# Uart_Can.net
KiCad netlist of a schematic drawn in Altium Designer
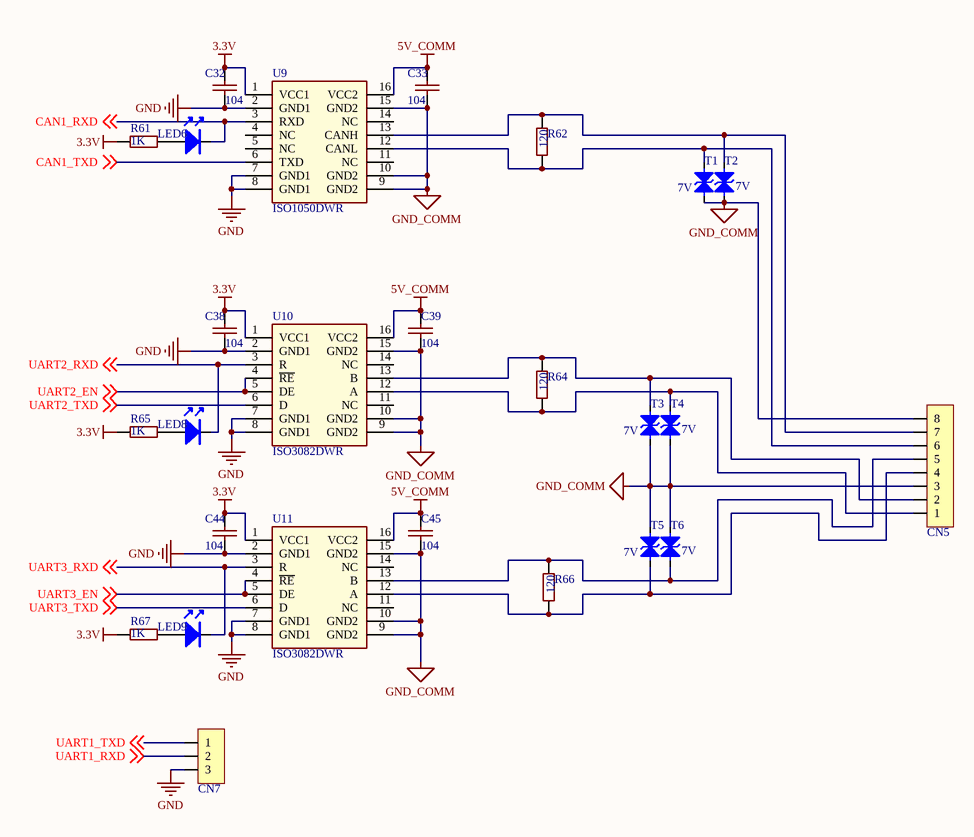
[diagram p0: Uart_Can.SchDoc]

(export (version "E")
  (design (tool "Eeschema 10.0.6"))
  (components
    (comp (ref "C32")
      (value "104")
      (footprint "0805SMD_Cap")
      (description "贴片电容")
      (libsource (lib "ST_GND_Sch") (part "SMD_Cap"))
    )
    (comp (ref "C33")
      (value "104")
      (footprint "0805SMD_Cap")
      (description "贴片电容")
      (libsource (lib "ST_GND_Sch") (part "SMD_Cap"))
    )
    (comp (ref "C38")
      (value "104")
      (footprint "0805SMD_Cap")
      (description "贴片电容")
      (libsource (lib "ST_GND_Sch") (part "SMD_Cap"))
    )
    (comp (ref "C39")
      (value "104")
      (footprint "0805SMD_Cap")
      (description "贴片电容")
      (libsource (lib "ST_GND_Sch") (part "SMD_Cap"))
    )
    (comp (ref "C44")
      (value "104")
      (footprint "0805SMD_Cap")
      (description "贴片电容")
      (libsource (lib "ST_GND_Sch") (part "SMD_Cap"))
    )
    (comp (ref "C45")
      (value "104")
      (footprint "0805SMD_Cap")
      (description "贴片电容")
      (libsource (lib "ST_GND_Sch") (part "SMD_Cap"))
    )
    (comp (ref "CN5")
      (value "CON8")
      (footprint "WJ15EDGRM-3.81-8P")
      (description "连接器")
      (libsource (lib "ST_GND_Sch") (part "CON8"))
    )
    (comp (ref "CN7")
      (value "CON3")
      (footprint "DIP3")
      (description "连接器")
      (libsource (lib "ST_GND_Sch") (part "CON3"))
    )
    (comp (ref "LED6")
      (value "LED")
      (footprint "发光二极管0805")
      (description "发光二极管")
      (libsource (lib "ST_GND_Sch") (part "LED"))
    )
    (comp (ref "LED8")
      (value "LED")
      (footprint "发光二极管0805")
      (description "发光二极管")
      (libsource (lib "ST_GND_Sch") (part "LED"))
    )
    (comp (ref "LED9")
      (value "LED")
      (footprint "发光二极管0805")
      (description "发光二极管")
      (libsource (lib "ST_GND_Sch") (part "LED"))
    )
    (comp (ref "R61")
      (value "1K")
      (footprint "0805_SMD_R")
      (description "贴片电阻")
      (libsource (lib "") (part "SMD_0805_1"))
    )
    (comp (ref "R62")
      (value "120")
      (footprint "0805_SMD_R")
      (description "贴片电阻")
      (libsource (lib "ST_GND_Sch") (part "SMD_0805"))
    )
    (comp (ref "R64")
      (value "120")
      (footprint "0805_SMD_R")
      (description "贴片电阻")
      (libsource (lib "ST_GND_Sch") (part "SMD_0805"))
    )
    (comp (ref "R65")
      (value "1K")
      (footprint "0805_SMD_R")
      (description "贴片电阻")
      (libsource (lib "") (part "SMD_0805_1"))
    )
    (comp (ref "R66")
      (value "120")
      (footprint "0805_SMD_R")
      (description "贴片电阻")
      (libsource (lib "ST_GND_Sch") (part "SMD_0805"))
    )
    (comp (ref "R67")
      (value "1K")
      (footprint "0805_SMD_R")
      (description "贴片电阻")
      (libsource (lib "") (part "SMD_0805_1"))
    )
    (comp (ref "T1")
      (value "7V")
      (footprint "二极管SMA")
      (description "双向TVS_?V(SMA)")
      (libsource (lib "ST_GND_Sch") (part "双向TVS_?V(SMA)"))
    )
    (comp (ref "T2")
      (value "7V")
      (footprint "二极管SMA")
      (description "双向TVS_?V(SMA)")
      (libsource (lib "ST_GND_Sch") (part "双向TVS_?V(SMA)"))
    )
    (comp (ref "T3")
      (value "7V")
      (footprint "二极管SMA")
      (description "双向TVS_?V(SMA)")
      (libsource (lib "ST_GND_Sch") (part "双向TVS_?V(SMA)"))
    )
    (comp (ref "T4")
      (value "7V")
      (footprint "二极管SMA")
      (description "双向TVS_?V(SMA)")
      (libsource (lib "ST_GND_Sch") (part "双向TVS_?V(SMA)"))
    )
    (comp (ref "T5")
      (value "7V")
      (footprint "二极管SMA")
      (description "双向TVS_?V(SMA)")
      (libsource (lib "ST_GND_Sch") (part "双向TVS_?V(SMA)"))
    )
    (comp (ref "T6")
      (value "7V")
      (footprint "二极管SMA")
      (description "双向TVS_?V(SMA)")
      (libsource (lib "ST_GND_Sch") (part "双向TVS_?V(SMA)"))
    )
    (comp (ref "U9")
      (value "ISO1050DWR")
      (footprint "SOIC_16")
      (description "CAN隔离芯片")
      (libsource (lib "ST_GND_Sch") (part "ISO1050DWR"))
    )
    (comp (ref "U10")
      (value "ISO3082DWR")
      (footprint "SOIC_16")
      (description "485隔离芯片")
      (libsource (lib "ST_GND_Sch") (part "ISO3082DWR"))
    )
    (comp (ref "U11")
      (value "ISO3082DWR")
      (footprint "SOIC_16")
      (description "485隔离芯片")
      (libsource (lib "ST_GND_Sch") (part "ISO3082DWR"))
    )
  )
  (nets
    (net (code "1") (name "3.3V") (class "Default")
      (node (ref "C32") (pin "2") (pintype "passive"))
      (node (ref "C38") (pin "2") (pintype "passive"))
      (node (ref "C44") (pin "2") (pintype "passive"))
      (node (ref "R61") (pin "2") (pinfunction "2_2") (pintype "passive"))
      (node (ref "R65") (pin "2") (pinfunction "2_2") (pintype "passive"))
      (node (ref "R67") (pin "2") (pinfunction "2_2") (pintype "passive"))
      (node (ref "U10") (pin "1") (pinfunction "VCC1_1") (pintype "passive"))
      (node (ref "U11") (pin "1") (pinfunction "VCC1_1") (pintype "passive"))
      (node (ref "U9") (pin "1") (pinfunction "VCC1_1") (pintype "passive"))
    )
    (net (code "2") (name "5V_COMM") (class "Default")
      (node (ref "C33") (pin "2") (pintype "passive"))
      (node (ref "C39") (pin "2") (pintype "passive"))
      (node (ref "C45") (pin "2") (pintype "passive"))
      (node (ref "U10") (pin "16") (pinfunction "VCC2_16") (pintype "passive"))
      (node (ref "U11") (pin "16") (pinfunction "VCC2_16") (pintype "passive"))
      (node (ref "U9") (pin "16") (pinfunction "VCC2_16") (pintype "passive"))
    )
    (net (code "3") (name "CAN1_RXD") (class "Default")
      (node (ref "LED6") (pin "K") (pintype "passive"))
      (node (ref "U9") (pin "3") (pinfunction "RXD_3") (pintype "passive"))
    )
    (net (code "4") (name "CAN1_TXD") (class "Default")
      (node (ref "U9") (pin "6") (pinfunction "TXD_6") (pintype "passive"))
    )
    (net (code "5") (name "GND") (class "Default")
      (node (ref "C32") (pin "1") (pintype "passive"))
      (node (ref "C38") (pin "1") (pintype "passive"))
      (node (ref "C44") (pin "1") (pintype "passive"))
      (node (ref "CN7") (pin "3") (pinfunction "3_3") (pintype "passive"))
      (node (ref "U10") (pin "2") (pinfunction "GND1_2") (pintype "passive"))
      (node (ref "U10") (pin "7") (pinfunction "GND1_7") (pintype "passive"))
      (node (ref "U10") (pin "8") (pinfunction "GND1_8") (pintype "passive"))
      (node (ref "U11") (pin "2") (pinfunction "GND1_2") (pintype "passive"))
      (node (ref "U11") (pin "7") (pinfunction "GND1_7") (pintype "passive"))
      (node (ref "U11") (pin "8") (pinfunction "GND1_8") (pintype "passive"))
      (node (ref "U9") (pin "2") (pinfunction "GND1_2") (pintype "passive"))
      (node (ref "U9") (pin "7") (pinfunction "GND1_7") (pintype "passive"))
      (node (ref "U9") (pin "8") (pinfunction "GND1_8") (pintype "passive"))
    )
    (net (code "6") (name "GND_COMM") (class "Default")
      (node (ref "C33") (pin "1") (pintype "passive"))
      (node (ref "C39") (pin "1") (pintype "passive"))
      (node (ref "C45") (pin "1") (pintype "passive"))
      (node (ref "CN5") (pin "3") (pinfunction "3_3") (pintype "passive"))
      (node (ref "CN5") (pin "8") (pinfunction "8_8") (pintype "passive"))
      (node (ref "T1") (pin "A") (pinfunction "A_A") (pintype "passive"))
      (node (ref "T2") (pin "A") (pinfunction "A_A") (pintype "passive"))
      (node (ref "T3") (pin "A") (pinfunction "A_A") (pintype "passive"))
      (node (ref "T4") (pin "A") (pinfunction "A_A") (pintype "passive"))
      (node (ref "T5") (pin "K") (pinfunction "K_K") (pintype "passive"))
      (node (ref "T6") (pin "K") (pinfunction "K_K") (pintype "passive"))
      (node (ref "U10") (pin "10") (pinfunction "GND2_10") (pintype "passive"))
      (node (ref "U10") (pin "15") (pinfunction "GND2_15") (pintype "passive"))
      (node (ref "U10") (pin "9") (pinfunction "GND2_9") (pintype "passive"))
      (node (ref "U11") (pin "10") (pinfunction "GND2_10") (pintype "passive"))
      (node (ref "U11") (pin "15") (pinfunction "GND2_15") (pintype "passive"))
      (node (ref "U11") (pin "9") (pinfunction "GND2_9") (pintype "passive"))
      (node (ref "U9") (pin "10") (pinfunction "GND2_10") (pintype "passive"))
      (node (ref "U9") (pin "15") (pinfunction "GND2_15") (pintype "passive"))
      (node (ref "U9") (pin "9") (pinfunction "GND2_9") (pintype "passive"))
    )
    (net (code "7") (name "Net-(LED6-PadA)") (class "Default")
      (node (ref "LED6") (pin "A") (pintype "passive"))
      (node (ref "R61") (pin "1") (pinfunction "1_1") (pintype "passive"))
    )
    (net (code "8") (name "Net-(LED8-PadA)") (class "Default")
      (node (ref "LED8") (pin "A") (pintype "passive"))
      (node (ref "R65") (pin "1") (pinfunction "1_1") (pintype "passive"))
    )
    (net (code "9") (name "Net-(LED9-PadA)") (class "Default")
      (node (ref "LED9") (pin "A") (pintype "passive"))
      (node (ref "R67") (pin "1") (pinfunction "1_1") (pintype "passive"))
    )
    (net (code "10") (name "Net-(U9-CANH)") (class "Default")
      (node (ref "CN5") (pin "7") (pinfunction "7_7") (pintype "passive"))
      (node (ref "R62") (pin "2") (pinfunction "2_2") (pintype "passive"))
      (node (ref "T2") (pin "K") (pinfunction "K_K") (pintype "passive"))
      (node (ref "U9") (pin "13") (pinfunction "CANH_13") (pintype "passive"))
    )
    (net (code "11") (name "Net-(U9-CANL)") (class "Default")
      (node (ref "CN5") (pin "6") (pinfunction "6_6") (pintype "passive"))
      (node (ref "R62") (pin "1") (pinfunction "1_1") (pintype "passive"))
      (node (ref "T1") (pin "K") (pinfunction "K_K") (pintype "passive"))
      (node (ref "U9") (pin "12") (pinfunction "CANL_12") (pintype "passive"))
    )
    (net (code "12") (name "Net-(U10-A)") (class "Default")
      (node (ref "CN5") (pin "1") (pinfunction "1_1") (pintype "passive"))
      (node (ref "R64") (pin "1") (pinfunction "1_1") (pintype "passive"))
      (node (ref "T4") (pin "K") (pinfunction "K_K") (pintype "passive"))
      (node (ref "U10") (pin "12") (pinfunction "A_12") (pintype "passive"))
    )
    (net (code "13") (name "Net-(U10-B)") (class "Default")
      (node (ref "CN5") (pin "2") (pinfunction "2_2") (pintype "passive"))
      (node (ref "R64") (pin "2") (pinfunction "2_2") (pintype "passive"))
      (node (ref "T3") (pin "K") (pinfunction "K_K") (pintype "passive"))
      (node (ref "U10") (pin "13") (pinfunction "B_13") (pintype "passive"))
    )
    (net (code "14") (name "Net-(U11-A)") (class "Default")
      (node (ref "CN5") (pin "4") (pinfunction "4_4") (pintype "passive"))
      (node (ref "R66") (pin "1") (pinfunction "1_1") (pintype "passive"))
      (node (ref "T5") (pin "A") (pinfunction "A_A") (pintype "passive"))
      (node (ref "U11") (pin "12") (pinfunction "A_12") (pintype "passive"))
    )
    (net (code "15") (name "Net-(U11-B)") (class "Default")
      (node (ref "CN5") (pin "5") (pinfunction "5_5") (pintype "passive"))
      (node (ref "R66") (pin "2") (pinfunction "2_2") (pintype "passive"))
      (node (ref "T6") (pin "A") (pinfunction "A_A") (pintype "passive"))
      (node (ref "U11") (pin "13") (pinfunction "B_13") (pintype "passive"))
    )
    (net (code "16") (name "UART1_RXD") (class "Default")
      (node (ref "CN7") (pin "2") (pinfunction "2_2") (pintype "passive"))
    )
    (net (code "17") (name "UART1_TXD") (class "Default")
      (node (ref "CN7") (pin "1") (pinfunction "1_1") (pintype "passive"))
    )
    (net (code "18") (name "UART2_EN") (class "Default")
      (node (ref "U10") (pin "4") (pinfunction "~{RE}_4") (pintype "passive"))
      (node (ref "U10") (pin "5") (pinfunction "DE_5") (pintype "passive"))
    )
    (net (code "19") (name "UART2_RXD") (class "Default")
      (node (ref "LED8") (pin "K") (pintype "passive"))
      (node (ref "U10") (pin "3") (pinfunction "R_3") (pintype "passive"))
    )
    (net (code "20") (name "UART2_TXD") (class "Default")
      (node (ref "U10") (pin "6") (pinfunction "D_6") (pintype "passive"))
    )
    (net (code "21") (name "UART3_EN") (class "Default")
      (node (ref "U11") (pin "4") (pinfunction "~{RE}_4") (pintype "passive"))
      (node (ref "U11") (pin "5") (pinfunction "DE_5") (pintype "passive"))
    )
    (net (code "22") (name "UART3_RXD") (class "Default")
      (node (ref "LED9") (pin "K") (pintype "passive"))
      (node (ref "U11") (pin "3") (pinfunction "R_3") (pintype "passive"))
    )
    (net (code "23") (name "UART3_TXD") (class "Default")
      (node (ref "U11") (pin "6") (pinfunction "D_6") (pintype "passive"))
    )
    (net (code "24") (name "unconnected-(U9-NC-Pad4)") (class "Default")
      (node (ref "U9") (pin "4") (pinfunction "NC_4") (pintype "passive"))
    )
    (net (code "25") (name "unconnected-(U9-NC-Pad5)") (class "Default")
      (node (ref "U9") (pin "5") (pinfunction "NC_5") (pintype "passive"))
    )
    (net (code "26") (name "unconnected-(U9-NC-Pad11)") (class "Default")
      (node (ref "U9") (pin "11") (pinfunction "NC_11") (pintype "passive"))
    )
    (net (code "27") (name "unconnected-(U9-NC-Pad14)") (class "Default")
      (node (ref "U9") (pin "14") (pinfunction "NC_14") (pintype "passive"))
    )
    (net (code "28") (name "unconnected-(U10-NC-Pad11)") (class "Default")
      (node (ref "U10") (pin "11") (pinfunction "NC_11") (pintype "passive"))
    )
    (net (code "29") (name "unconnected-(U10-NC-Pad14)") (class "Default")
      (node (ref "U10") (pin "14") (pinfunction "NC_14") (pintype "passive"))
    )
    (net (code "30") (name "unconnected-(U11-NC-Pad11)") (class "Default")
      (node (ref "U11") (pin "11") (pinfunction "NC_11") (pintype "passive"))
    )
    (net (code "31") (name "unconnected-(U11-NC-Pad14)") (class "Default")
      (node (ref "U11") (pin "14") (pinfunction "NC_14") (pintype "passive"))
    )
  )
)
